# LED-strip.net
KiCad netlist of a schematic drawn in EAGLE
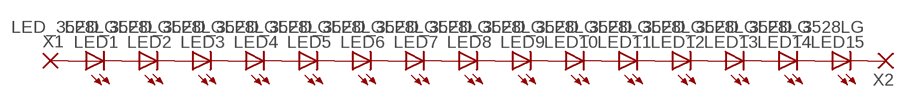
[diagram p0: schematic, sheet 1]

(export (version "E")
  (design (tool "Eeschema 10.0.6"))
  (components
    (comp (ref "LED1")
      (value "LED_3528LG")
      (footprint "eagle-import:LED2835_LG")
      (libsource (lib "eagle-import") (part "LED_3528LG"))
    )
    (comp (ref "LED2")
      (value "LED_3528LG")
      (footprint "eagle-import:LED2835_LG")
      (libsource (lib "eagle-import") (part "LED_3528LG"))
    )
    (comp (ref "LED3")
      (value "LED_3528LG")
      (footprint "eagle-import:LED2835_LG")
      (libsource (lib "eagle-import") (part "LED_3528LG"))
    )
    (comp (ref "LED4")
      (value "LED_3528LG")
      (footprint "eagle-import:LED2835_LG")
      (libsource (lib "eagle-import") (part "LED_3528LG"))
    )
    (comp (ref "LED5")
      (value "LED_3528LG")
      (footprint "eagle-import:LED2835_LG")
      (libsource (lib "eagle-import") (part "LED_3528LG"))
    )
    (comp (ref "LED6")
      (value "LED_3528LG")
      (footprint "eagle-import:LED2835_LG")
      (libsource (lib "eagle-import") (part "LED_3528LG"))
    )
    (comp (ref "LED7")
      (value "LED_3528LG")
      (footprint "eagle-import:LED2835_LG")
      (libsource (lib "eagle-import") (part "LED_3528LG"))
    )
    (comp (ref "LED8")
      (value "LED_3528LG")
      (footprint "eagle-import:LED2835_LG")
      (libsource (lib "eagle-import") (part "LED_3528LG"))
    )
    (comp (ref "LED9")
      (value "LED_3528LG")
      (footprint "eagle-import:LED2835_LG")
      (libsource (lib "eagle-import") (part "LED_3528LG"))
    )
    (comp (ref "LED10")
      (value "LED_3528LG")
      (footprint "eagle-import:LED2835_LG")
      (libsource (lib "eagle-import") (part "LED_3528LG"))
    )
    (comp (ref "LED11")
      (value "LED_3528LG")
      (footprint "eagle-import:LED2835_LG")
      (libsource (lib "eagle-import") (part "LED_3528LG"))
    )
    (comp (ref "LED12")
      (value "LED_3528LG")
      (footprint "eagle-import:LED2835_LG")
      (libsource (lib "eagle-import") (part "LED_3528LG"))
    )
    (comp (ref "LED13")
      (value "LED_3528LG")
      (footprint "eagle-import:LED2835_LG")
      (libsource (lib "eagle-import") (part "LED_3528LG"))
    )
    (comp (ref "LED14")
      (value "LED_3528LG")
      (footprint "eagle-import:LED2835_LG")
      (libsource (lib "eagle-import") (part "LED_3528LG"))
    )
    (comp (ref "LED15")
      (value "LED_3528LG")
      (footprint "eagle-import:LED2835_LG")
      (libsource (lib "eagle-import") (part "LED_3528LG"))
    )
    (comp (ref "X1")
      (value "WIREPAD-SMD2")
      (footprint "eagle-import:PAD-1.27X2.54")
      (libsource (lib "eagle-import") (part "WIREPAD-SMD2"))
    )
    (comp (ref "X2")
      (value "WIREPAD-SMD2")
      (footprint "eagle-import:PAD-1.27X2.54")
      (libsource (lib "eagle-import") (part "WIREPAD-SMD2"))
    )
  )
  (nets
    (net (code "1") (name "Net-(LED1-PadC)") (class "Default")
      (node (ref "LED1") (pin "C") (pinfunction "C_C") (pintype "passive"))
      (node (ref "LED2") (pin "A") (pinfunction "A_A") (pintype "passive"))
    )
    (net (code "2") (name "Net-(LED2-PadC)") (class "Default")
      (node (ref "LED2") (pin "C") (pinfunction "C_C") (pintype "passive"))
      (node (ref "LED3") (pin "A") (pinfunction "A_A") (pintype "passive"))
    )
    (net (code "3") (name "Net-(LED3-PadC)") (class "Default")
      (node (ref "LED3") (pin "C") (pinfunction "C_C") (pintype "passive"))
      (node (ref "LED4") (pin "A") (pinfunction "A_A") (pintype "passive"))
    )
    (net (code "4") (name "Net-(LED4-PadC)") (class "Default")
      (node (ref "LED4") (pin "C") (pinfunction "C_C") (pintype "passive"))
      (node (ref "LED5") (pin "A") (pinfunction "A_A") (pintype "passive"))
    )
    (net (code "5") (name "Net-(LED5-PadC)") (class "Default")
      (node (ref "LED5") (pin "C") (pinfunction "C_C") (pintype "passive"))
      (node (ref "LED6") (pin "A") (pinfunction "A_A") (pintype "passive"))
    )
    (net (code "6") (name "Net-(LED6-PadC)") (class "Default")
      (node (ref "LED6") (pin "C") (pinfunction "C_C") (pintype "passive"))
      (node (ref "LED7") (pin "A") (pinfunction "A_A") (pintype "passive"))
    )
    (net (code "7") (name "Net-(LED7-PadC)") (class "Default")
      (node (ref "LED7") (pin "C") (pinfunction "C_C") (pintype "passive"))
      (node (ref "LED8") (pin "A") (pinfunction "A_A") (pintype "passive"))
    )
    (net (code "8") (name "Net-(LED8-PadC)") (class "Default")
      (node (ref "LED8") (pin "C") (pinfunction "C_C") (pintype "passive"))
      (node (ref "LED9") (pin "A") (pinfunction "A_A") (pintype "passive"))
    )
    (net (code "9") (name "Net-(LED10-PadA)") (class "Default")
      (node (ref "LED10") (pin "A") (pinfunction "A_A") (pintype "passive"))
      (node (ref "LED9") (pin "C") (pinfunction "C_C") (pintype "passive"))
    )
    (net (code "10") (name "Net-(LED10-PadC)") (class "Default")
      (node (ref "LED10") (pin "C") (pinfunction "C_C") (pintype "passive"))
      (node (ref "LED11") (pin "A") (pinfunction "A_A") (pintype "passive"))
    )
    (net (code "11") (name "Net-(LED11-PadC)") (class "Default")
      (node (ref "LED11") (pin "C") (pinfunction "C_C") (pintype "passive"))
      (node (ref "LED12") (pin "A") (pinfunction "A_A") (pintype "passive"))
    )
    (net (code "12") (name "Net-(LED12-PadC)") (class "Default")
      (node (ref "LED12") (pin "C") (pinfunction "C_C") (pintype "passive"))
      (node (ref "LED13") (pin "A") (pinfunction "A_A") (pintype "passive"))
    )
    (net (code "13") (name "Net-(LED13-PadC)") (class "Default")
      (node (ref "LED13") (pin "C") (pinfunction "C_C") (pintype "passive"))
      (node (ref "LED14") (pin "A") (pinfunction "A_A") (pintype "passive"))
    )
    (net (code "14") (name "Net-(LED14-PadC)") (class "Default")
      (node (ref "LED14") (pin "C") (pinfunction "C_C") (pintype "passive"))
      (node (ref "LED15") (pin "A") (pinfunction "A_A") (pintype "passive"))
    )
    (net (code "15") (name "Net-(X1-P)") (class "Default")
      (node (ref "LED1") (pin "A") (pinfunction "A_A") (pintype "passive"))
      (node (ref "X1") (pin "P$1") (pinfunction "P_P$1") (pintype "passive"))
    )
    (net (code "16") (name "Net-(X2-P)") (class "Default")
      (node (ref "LED15") (pin "C") (pinfunction "C_C") (pintype "passive"))
      (node (ref "X2") (pin "P$1") (pinfunction "P_P$1") (pintype "passive"))
    )
  )
)
